# Sheet1.net
KiCad netlist of a schematic drawn in Altium Designer
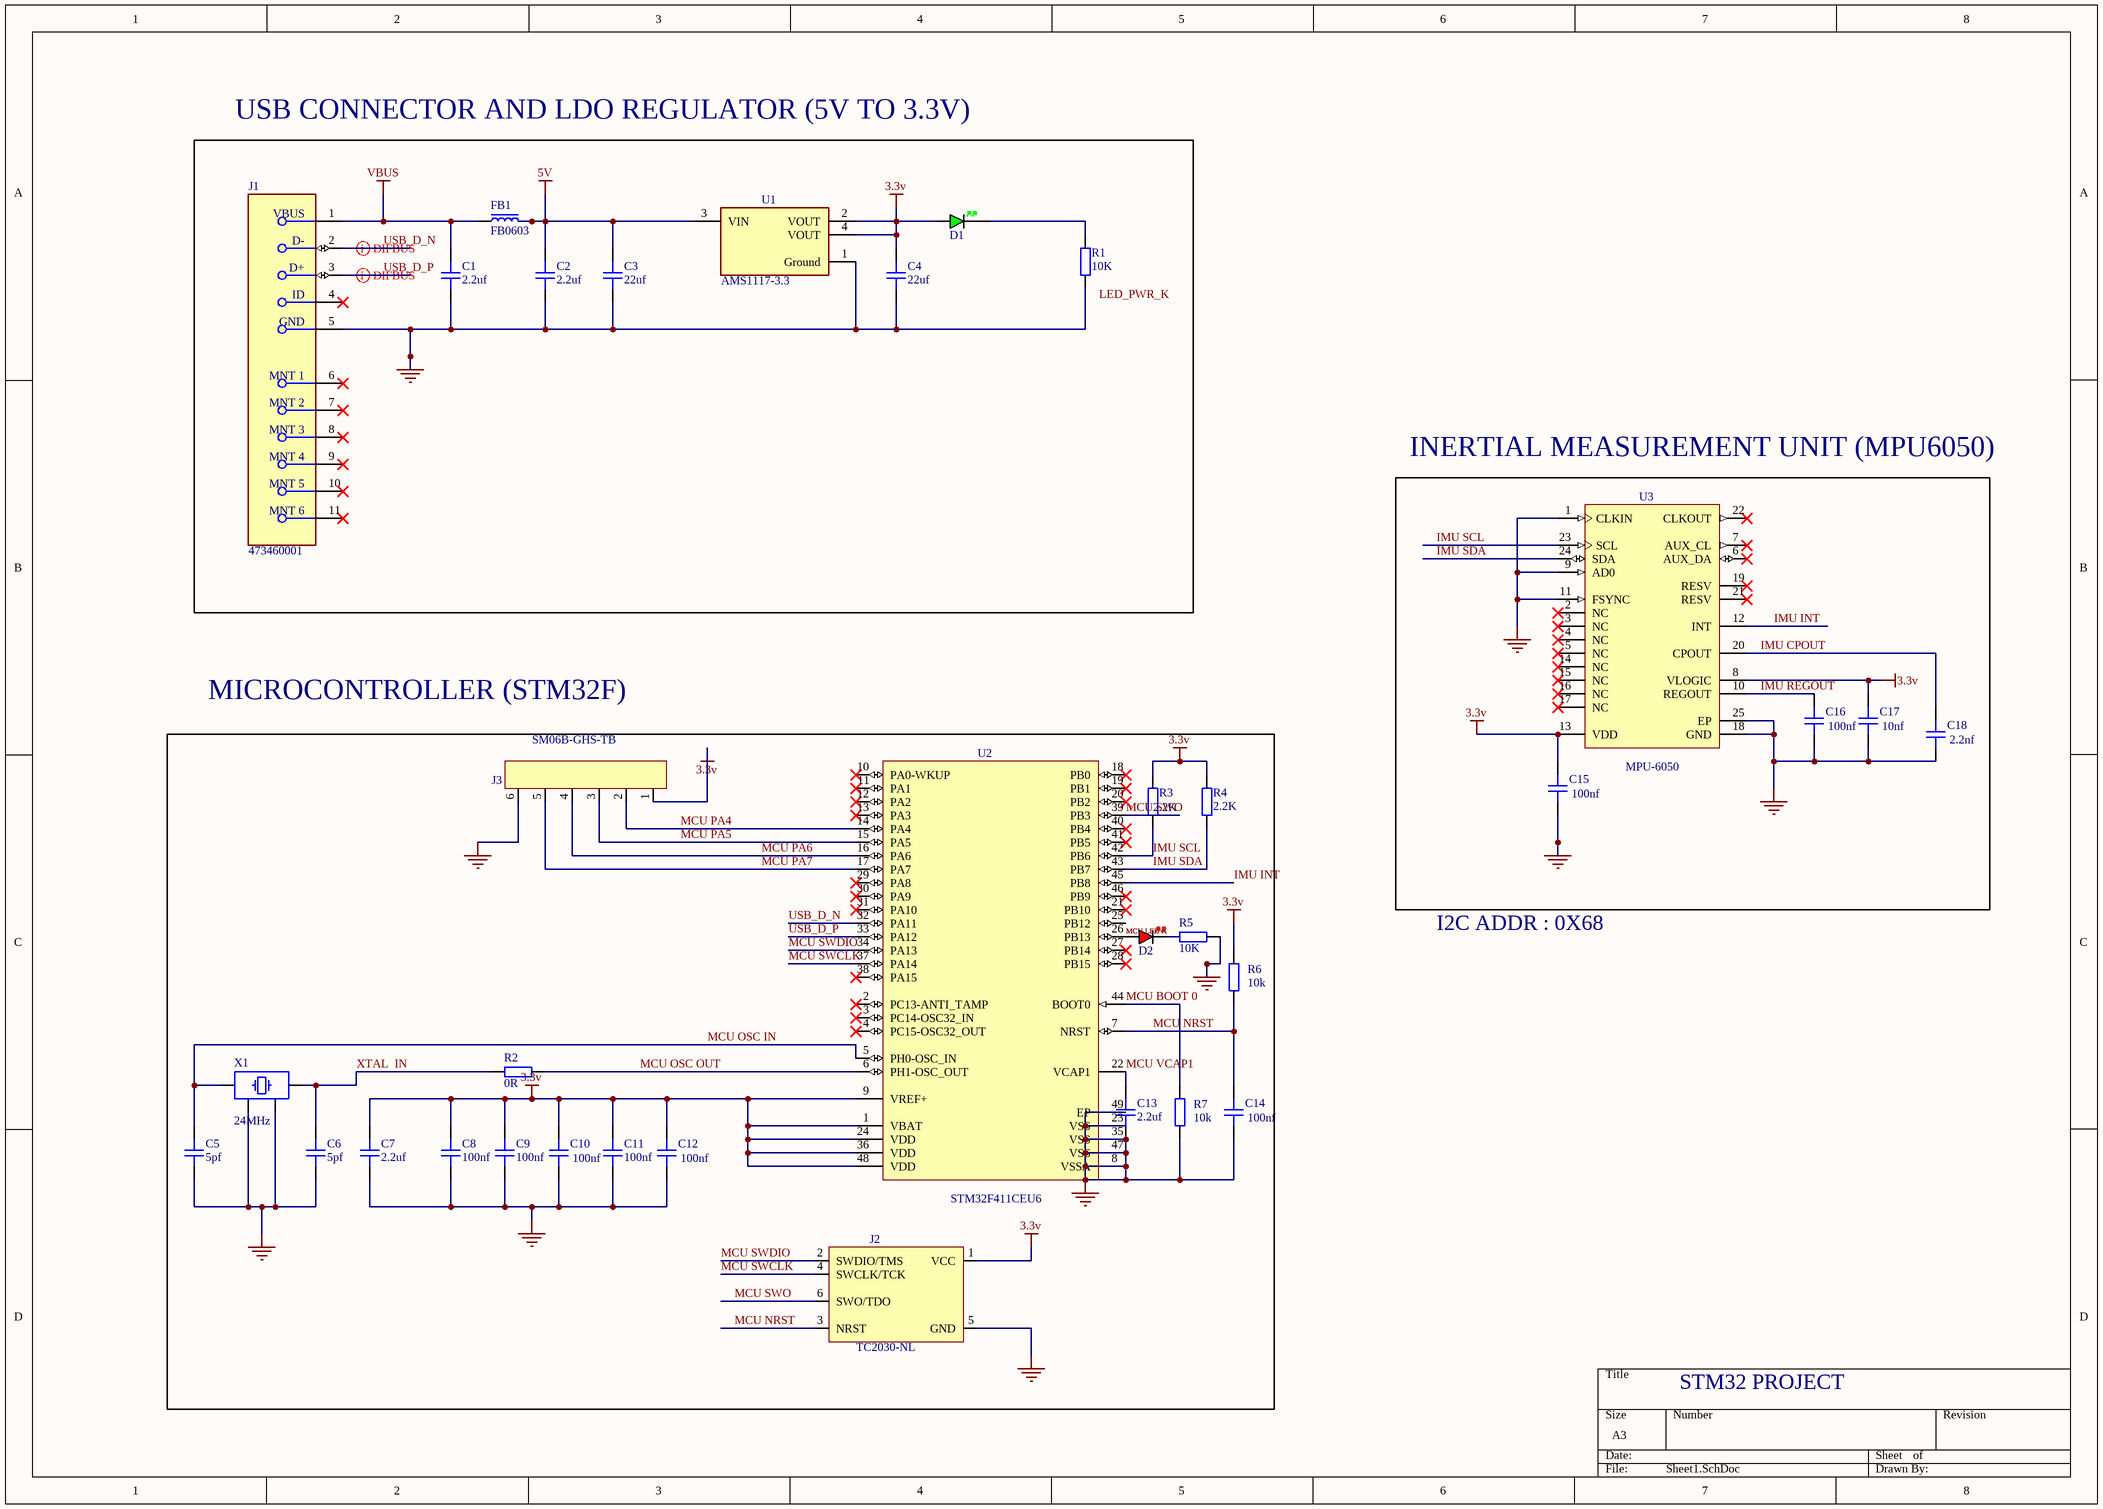
[diagram p0: Sheet1.SchDoc]

(export (version "E")
  (design (tool "Eeschema 10.0.6"))
  (components
    (comp (ref "C1")
      (value "2.2uf")
      (footprint "CAP_0603")
      (description "Capacitor SMD 0603")
      (libsource (lib "Schematic-Lib-PhilsLab") (part "CAP_0603"))
    )
    (comp (ref "C2")
      (value "2.2uf")
      (footprint "CAP_0603")
      (description "Capacitor SMD 0603")
      (libsource (lib "Schematic-Lib-PhilsLab") (part "CAP_0603"))
    )
    (comp (ref "C3")
      (value "22uf")
      (footprint "CAP_0805")
      (description "Capacitor SMD 0805")
      (libsource (lib "Schematic-Lib-PhilsLab") (part "CAP_0805"))
    )
    (comp (ref "C4")
      (value "22uf")
      (footprint "CAP_0805")
      (description "Capacitor SMD 0805")
      (libsource (lib "Schematic-Lib-PhilsLab") (part "CAP_0805"))
    )
    (comp (ref "C5")
      (value "5pf")
      (footprint "CAP_0402")
      (description "Capacitor SMD 0402")
      (libsource (lib "Schematic-Lib-PhilsLab") (part "CAP_0402"))
    )
    (comp (ref "C6")
      (value "5pf")
      (footprint "CAP_0402")
      (description "Capacitor SMD 0402")
      (libsource (lib "Schematic-Lib-PhilsLab") (part "CAP_0402"))
    )
    (comp (ref "C7")
      (value "2.2uf")
      (footprint "CAP_0603")
      (description "Capacitor SMD 0603")
      (libsource (lib "Schematic-Lib-PhilsLab") (part "CAP_0603"))
    )
    (comp (ref "C8")
      (value "100nf")
      (footprint "CAP_0402")
      (description "Capacitor SMD 0402")
      (libsource (lib "Schematic-Lib-PhilsLab") (part "CAP_0402"))
    )
    (comp (ref "C9")
      (value "100nf")
      (footprint "CAP_0402")
      (description "Capacitor SMD 0402")
      (libsource (lib "Schematic-Lib-PhilsLab") (part "CAP_0402"))
    )
    (comp (ref "C10")
      (value "100nf")
      (footprint "CAP_0402")
      (description "Capacitor SMD 0402")
      (libsource (lib "Schematic-Lib-PhilsLab") (part "CAP_0402"))
    )
    (comp (ref "C11")
      (value "100nf")
      (footprint "CAP_0402")
      (description "Capacitor SMD 0402")
      (libsource (lib "Schematic-Lib-PhilsLab") (part "CAP_0402"))
    )
    (comp (ref "C12")
      (value "100nf")
      (footprint "CAP_0402")
      (description "Capacitor SMD 0402")
      (libsource (lib "Schematic-Lib-PhilsLab") (part "CAP_0402"))
    )
    (comp (ref "C13")
      (value "2.2uf")
      (footprint "CAP_0603")
      (description "Capacitor SMD 0603")
      (libsource (lib "Schematic-Lib-PhilsLab") (part "CAP_0603"))
    )
    (comp (ref "C14")
      (value "100nf")
      (footprint "CAP_0402")
      (description "Capacitor SMD 0402")
      (libsource (lib "Schematic-Lib-PhilsLab") (part "CAP_0402"))
    )
    (comp (ref "C15")
      (value "100nf")
      (footprint "CAP_0402")
      (description "Capacitor SMD 0402")
      (libsource (lib "Schematic-Lib-PhilsLab") (part "CAP_0402"))
    )
    (comp (ref "C16")
      (value "100nf")
      (footprint "CAP_0402")
      (description "Capacitor SMD 0402")
      (libsource (lib "Schematic-Lib-PhilsLab") (part "CAP_0402"))
    )
    (comp (ref "C17")
      (value "10nf")
      (footprint "CAP_0402")
      (description "Capacitor SMD 0402")
      (libsource (lib "Schematic-Lib-PhilsLab") (part "CAP_0402"))
    )
    (comp (ref "C18")
      (value "2.2nf")
      (footprint "CAP_0402")
      (description "Capacitor SMD 0402")
      (libsource (lib "Schematic-Lib-PhilsLab") (part "CAP_0402"))
    )
    (comp (ref "D1")
      (value "GREEN")
      (footprint "LED_0402_GREEN")
      (description "LED 0402 GREEN SMD")
      (libsource (lib "Schematic-Lib-PhilsLab") (part "LED_0402_GREEN"))
    )
    (comp (ref "D2")
      (value "RED")
      (footprint "LED_0402_RED")
      (description "LED 0402 RED SMD")
      (libsource (lib "Schematic-Lib-PhilsLab") (part "LED_0402_RED"))
    )
    (comp (ref "FB1")
      (value "FB0603")
      (footprint "FB_0603")
      (description "Ferrite Bead SMD 0603")
      (libsource (lib "Schematic-Lib-PhilsLab") (part "FB_0603"))
    )
    (comp (ref "J1")
      (value "473460001")
      (footprint "FP-473460001-MFG")
      (description "CONN RCPT USB2.0 MICRO B SMD R/A")
      (fields
        (field (name "OCTOPART") "https://octopart.com/47346-0001-molex-7164928")
        (field (name "MANUFACTURER") "Molex")
      )
      (libsource (lib "Altium Content Vault") (part "53ae1f1d9b557310b43ca686e5bb76a"))
    )
    (comp (ref "J2")
      (value "TC2030-NL")
      (footprint "TC2030-NL-FP")
      (description "Tag-Connect No-Solder SWD Debug Connector (No Legs) DO NOT PLACE")
      (fields
        (field (name "MANUFACTURER") "Tag-Connect")
        (field (name "MANUFACTURER PART NUMBER") "TC2030-NL-FP")
      )
      (libsource (lib "Schematic-Lib-PhilsLab") (part "TC2030-NL"))
    )
    (comp (ref "J3")
      (value "SM06B-GHS-TB")
      (footprint "SM06B-GHS-TB")
      (description "Header Connector 6 Position 1.25MM Pitch SMD Horizontal JST GH")
      (fields (field (name "MANUFACTURER") "JST"))
      (libsource (lib "Schematic-Lib-PhilsLab") (part "SM06B-GHS-TB"))
    )
    (comp (ref "R1")
      (value "10K")
      (footprint "RES_0402")
      (description "Resistor SMD 0402")
      (libsource (lib "Schematic-Lib-PhilsLab") (part "RES_0402"))
    )
    (comp (ref "R2")
      (value "0R")
      (footprint "RES_0402")
      (description "Resistor SMD 0402")
      (libsource (lib "Schematic-Lib-PhilsLab") (part "RES_0402"))
    )
    (comp (ref "R3")
      (value "2.2K")
      (footprint "RES_0402")
      (description "Resistor SMD 0402")
      (libsource (lib "Schematic-Lib-PhilsLab") (part "RES_0402"))
    )
    (comp (ref "R4")
      (value "2.2K")
      (footprint "RES_0402")
      (description "Resistor SMD 0402")
      (libsource (lib "Schematic-Lib-PhilsLab") (part "RES_0402"))
    )
    (comp (ref "R5")
      (value "10K")
      (footprint "RES_0402")
      (description "Resistor SMD 0402")
      (libsource (lib "Schematic-Lib-PhilsLab") (part "RES_0402"))
    )
    (comp (ref "R6")
      (value "10k")
      (footprint "RES_0402")
      (description "Resistor SMD 0402")
      (libsource (lib "Schematic-Lib-PhilsLab") (part "RES_0402"))
    )
    (comp (ref "R7")
      (value "10k")
      (footprint "RES_0402")
      (description "Resistor SMD 0402")
      (libsource (lib "Schematic-Lib-PhilsLab") (part "RES_0402"))
    )
    (comp (ref "U1")
      (value "AMS1117-3.3")
      (footprint "FP-AMS1117-IPC_C")
      (description "LDO Voltage Regulators 1A, 3.3V")
      (fields
        (field (name "OCTOPART") "https://octopart.com/ams1117-3.3-advanced+monolithic+systems-25899300")
        (field (name "MANUFACTURER") "Advanced Monolithic Systems")
      )
      (libsource (lib "Altium Content Vault") (part "8bdbb5f8e77002000e30dd2845d0354"))
    )
    (comp (ref "U2")
      (value "STM32F411CEU6")
      (footprint "STM-UFQFPN48_L")
      (libsource (lib "Altium Content Vault") (part "MC-ARM-STM32F411-UFQFPN48"))
    )
    (comp (ref "U3")
      (value "MPU-6050")
      (footprint "IS-QFN-24_V")
      (fields (field (name "MANUFACTURER") "InvenSense"))
      (libsource (lib "Altium Content Vault") (part "IS-MPU-6050-QFN-24"))
    )
    (comp (ref "X1")
      (value "24MHz")
      (footprint "XTAL_3225")
      (description "Crystal SMD 24MHz 10PPM 7pF 3225")
      (fields
        (field (name "MANUFACTURER") "Epson")
        (field (name "MANUFACTURER PART NUMBER") "TSX-3225 24.0000MF15X-AC")
      )
      (libsource (lib "Schematic-Lib-PhilsLab") (part "TSX-3225_24.0000MF15X-AC"))
    )
  )
  (nets
    (net (code "1") (name "/IMU CPOUT") (class "Default")
      (node (ref "C18") (pin "2") (pinfunction "2_2") (pintype "passive"))
      (node (ref "U3") (pin "20") (pinfunction "CPOUT_20") (pintype "passive"))
    )
    (net (code "2") (name "/IMU INT") (class "Default")
      (node (ref "U2") (pin "45") (pinfunction "PB8_45") (pintype "bidirectional"))
      (node (ref "U3") (pin "12") (pinfunction "INT_12") (pintype "open_collector"))
    )
    (net (code "3") (name "/IMU REGOUT") (class "Default")
      (node (ref "C16") (pin "2") (pinfunction "2_2") (pintype "passive"))
      (node (ref "U3") (pin "10") (pinfunction "REGOUT_10") (pintype "passive"))
    )
    (net (code "4") (name "/IMU SCL") (class "Default")
      (node (ref "R3") (pin "1") (pinfunction "1_1") (pintype "passive"))
      (node (ref "U2") (pin "42") (pinfunction "PB6_42") (pintype "bidirectional"))
      (node (ref "U3") (pin "23") (pinfunction "SCL_23") (pintype "input"))
    )
    (net (code "5") (name "/IMU SDA") (class "Default")
      (node (ref "R4") (pin "1") (pinfunction "1_1") (pintype "passive"))
      (node (ref "U2") (pin "43") (pinfunction "PB7_43") (pintype "bidirectional"))
      (node (ref "U3") (pin "24") (pinfunction "SDA_24") (pintype "bidirectional"))
    )
    (net (code "7") (name "/MCU BOOT 0") (class "Default")
      (node (ref "R7") (pin "1") (pinfunction "1_1") (pintype "passive"))
      (node (ref "U2") (pin "44") (pinfunction "BOOT0_44") (pintype "input"))
    )
    (net (code "8") (name "/MCU LED A") (class "Default")
      (node (ref "D2") (pin "A") (pinfunction "A_A") (pintype "passive"))
      (node (ref "U2") (pin "26") (pinfunction "PB13_26") (pintype "bidirectional"))
    )
    (net (code "9") (name "/MCU NRST") (class "Default")
      (node (ref "C14") (pin "2") (pinfunction "2_2") (pintype "passive"))
      (node (ref "J2") (pin "3") (pinfunction "NRST_3") (pintype "passive"))
      (node (ref "R6") (pin "2") (pinfunction "2_2") (pintype "passive"))
      (node (ref "U2") (pin "7") (pinfunction "NRST_7") (pintype "bidirectional"))
    )
    (net (code "10") (name "/MCU OSC IN") (class "Default")
      (node (ref "C5") (pin "2") (pinfunction "2_2") (pintype "passive"))
      (node (ref "U2") (pin "5") (pinfunction "PH0-OSC_IN_5") (pintype "bidirectional"))
      (node (ref "X1") (pin "1") (pinfunction "1_1") (pintype "passive"))
    )
    (net (code "11") (name "/MCU OSC OUT") (class "Default")
      (node (ref "R2") (pin "2") (pinfunction "2_2") (pintype "passive"))
      (node (ref "U2") (pin "6") (pinfunction "PH1-OSC_OUT_6") (pintype "bidirectional"))
    )
    (net (code "12") (name "/MCU PA4") (class "Default")
      (node (ref "J3") (pin "2") (pinfunction "2_2") (pintype "passive"))
      (node (ref "U2") (pin "14") (pinfunction "PA4_14") (pintype "bidirectional"))
    )
    (net (code "13") (name "/MCU PA5") (class "Default")
      (node (ref "J3") (pin "3") (pinfunction "3_3") (pintype "passive"))
      (node (ref "U2") (pin "15") (pinfunction "PA5_15") (pintype "bidirectional"))
    )
    (net (code "14") (name "/MCU PA6") (class "Default")
      (node (ref "J3") (pin "4") (pinfunction "4_4") (pintype "passive"))
      (node (ref "U2") (pin "16") (pinfunction "PA6_16") (pintype "bidirectional"))
    )
    (net (code "15") (name "/MCU PA7") (class "Default")
      (node (ref "J3") (pin "5") (pinfunction "5_5") (pintype "passive"))
      (node (ref "U2") (pin "17") (pinfunction "PA7_17") (pintype "bidirectional"))
    )
    (net (code "16") (name "/MCU SWCLK") (class "Default")
      (node (ref "J2") (pin "4") (pinfunction "SWCLK/TCK_4") (pintype "passive"))
      (node (ref "U2") (pin "37") (pinfunction "PA14_37") (pintype "bidirectional"))
    )
    (net (code "17") (name "/MCU SWDIO") (class "Default")
      (node (ref "J2") (pin "2") (pinfunction "SWDIO/TMS_2") (pintype "passive"))
      (node (ref "U2") (pin "34") (pinfunction "PA13_34") (pintype "bidirectional"))
    )
    (net (code "18") (name "/MCU SWO") (class "Default")
      (node (ref "J2") (pin "6") (pinfunction "SWO/TDO_6") (pintype "passive"))
      (node (ref "U2") (pin "39") (pinfunction "PB3_39") (pintype "bidirectional"))
    )
    (net (code "19") (name "/MCU VCAP1") (class "Default")
      (node (ref "C13") (pin "2") (pinfunction "2_2") (pintype "passive"))
      (node (ref "U2") (pin "22") (pinfunction "VCAP1_22") (pintype "passive"))
    )
    (net (code "20") (name "/USB_D_N") (class "Default")
      (node (ref "J1") (pin "2") (pinfunction "D-_2") (pintype "bidirectional"))
      (node (ref "U2") (pin "32") (pinfunction "PA11_32") (pintype "bidirectional"))
    )
    (net (code "21") (name "/USB_D_P") (class "Default")
      (node (ref "J1") (pin "3") (pinfunction "D+_3") (pintype "bidirectional"))
      (node (ref "U2") (pin "33") (pinfunction "PA12_33") (pintype "bidirectional"))
    )
    (net (code "22") (name "/XTAL  IN") (class "Default")
      (node (ref "C6") (pin "2") (pinfunction "2_2") (pintype "passive"))
      (node (ref "R2") (pin "1") (pinfunction "1_1") (pintype "passive"))
      (node (ref "X1") (pin "3") (pinfunction "3_3") (pintype "passive"))
    )
    (net (code "23") (name "3.3v") (class "Default")
      (node (ref "C10") (pin "2") (pinfunction "2_2") (pintype "passive"))
      (node (ref "C11") (pin "2") (pinfunction "2_2") (pintype "passive"))
      (node (ref "C12") (pin "2") (pinfunction "2_2") (pintype "passive"))
      (node (ref "C15") (pin "2") (pinfunction "2_2") (pintype "passive"))
      (node (ref "C17") (pin "2") (pinfunction "2_2") (pintype "passive"))
      (node (ref "C4") (pin "2") (pinfunction "2_2") (pintype "passive"))
      (node (ref "C7") (pin "2") (pinfunction "2_2") (pintype "passive"))
      (node (ref "C8") (pin "2") (pinfunction "2_2") (pintype "passive"))
      (node (ref "C9") (pin "2") (pinfunction "2_2") (pintype "passive"))
      (node (ref "D1") (pin "A") (pinfunction "A_A") (pintype "passive"))
      (node (ref "J2") (pin "1") (pinfunction "VCC_1") (pintype "passive"))
      (node (ref "J3") (pin "1") (pinfunction "1_1") (pintype "passive"))
      (node (ref "R3") (pin "2") (pinfunction "2_2") (pintype "passive"))
      (node (ref "R4") (pin "2") (pinfunction "2_2") (pintype "passive"))
      (node (ref "R6") (pin "1") (pinfunction "1_1") (pintype "passive"))
      (node (ref "U1") (pin "2") (pinfunction "VOUT_2") (pintype "passive"))
      (node (ref "U1") (pin "4") (pinfunction "VOUT_4") (pintype "passive"))
      (node (ref "U2") (pin "1") (pinfunction "VBAT_1") (pintype "power_in"))
      (node (ref "U2") (pin "24") (pinfunction "VDD_24") (pintype "power_in"))
      (node (ref "U2") (pin "36") (pinfunction "VDD_36") (pintype "power_in"))
      (node (ref "U2") (pin "48") (pinfunction "VDD_48") (pintype "power_in"))
      (node (ref "U2") (pin "9") (pinfunction "VREF+_9") (pintype "power_in"))
      (node (ref "U3") (pin "13") (pinfunction "VDD_13") (pintype "power_in"))
      (node (ref "U3") (pin "8") (pinfunction "VLOGIC_8") (pintype "power_in"))
    )
    (net (code "24") (name "5V") (class "Default")
      (node (ref "C2") (pin "2") (pinfunction "2_2") (pintype "passive"))
      (node (ref "C3") (pin "2") (pinfunction "2_2") (pintype "passive"))
      (node (ref "FB1") (pin "2") (pinfunction "2_2") (pintype "passive"))
      (node (ref "U1") (pin "3") (pinfunction "VIN_3") (pintype "power_in"))
    )
    (net (code "25") (name "GND") (class "Default")
      (node (ref "C1") (pin "1") (pinfunction "1_1") (pintype "passive"))
      (node (ref "C10") (pin "1") (pinfunction "1_1") (pintype "passive"))
      (node (ref "C11") (pin "1") (pinfunction "1_1") (pintype "passive"))
      (node (ref "C12") (pin "1") (pinfunction "1_1") (pintype "passive"))
      (node (ref "C13") (pin "1") (pinfunction "1_1") (pintype "passive"))
      (node (ref "C14") (pin "1") (pinfunction "1_1") (pintype "passive"))
      (node (ref "C15") (pin "1") (pinfunction "1_1") (pintype "passive"))
      (node (ref "C16") (pin "1") (pinfunction "1_1") (pintype "passive"))
      (node (ref "C17") (pin "1") (pinfunction "1_1") (pintype "passive"))
      (node (ref "C18") (pin "1") (pinfunction "1_1") (pintype "passive"))
      (node (ref "C2") (pin "1") (pinfunction "1_1") (pintype "passive"))
      (node (ref "C3") (pin "1") (pinfunction "1_1") (pintype "passive"))
      (node (ref "C4") (pin "1") (pinfunction "1_1") (pintype "passive"))
      (node (ref "C5") (pin "1") (pinfunction "1_1") (pintype "passive"))
      (node (ref "C6") (pin "1") (pinfunction "1_1") (pintype "passive"))
      (node (ref "C7") (pin "1") (pinfunction "1_1") (pintype "passive"))
      (node (ref "C8") (pin "1") (pinfunction "1_1") (pintype "passive"))
      (node (ref "C9") (pin "1") (pinfunction "1_1") (pintype "passive"))
      (node (ref "J1") (pin "5") (pinfunction "GND_5") (pintype "power_in"))
      (node (ref "J2") (pin "5") (pinfunction "GND_5") (pintype "passive"))
      (node (ref "J3") (pin "6") (pinfunction "6_6") (pintype "passive"))
      (node (ref "R1") (pin "1") (pinfunction "1_1") (pintype "passive"))
      (node (ref "R5") (pin "1") (pinfunction "1_1") (pintype "passive"))
      (node (ref "R7") (pin "2") (pinfunction "2_2") (pintype "passive"))
      (node (ref "U1") (pin "1") (pinfunction "Ground_1") (pintype "power_in"))
      (node (ref "U2") (pin "23") (pinfunction "VSS_23") (pintype "power_in"))
      (node (ref "U2") (pin "35") (pinfunction "VSS_35") (pintype "power_in"))
      (node (ref "U2") (pin "47") (pinfunction "VSS_47") (pintype "power_in"))
      (node (ref "U2") (pin "49") (pinfunction "EP_49") (pintype "power_in"))
      (node (ref "U2") (pin "8") (pinfunction "VSSA_8") (pintype "power_in"))
      (node (ref "U3") (pin "1") (pinfunction "CLKIN_1") (pintype "input"))
      (node (ref "U3") (pin "11") (pinfunction "FSYNC_11") (pintype "input"))
      (node (ref "U3") (pin "18") (pinfunction "GND_18") (pintype "power_in"))
      (node (ref "U3") (pin "25") (pinfunction "EP_25") (pintype "power_in"))
      (node (ref "U3") (pin "9") (pinfunction "AD0_9") (pintype "input"))
      (node (ref "X1") (pin "2") (pinfunction "2_2") (pintype "passive"))
      (node (ref "X1") (pin "4") (pinfunction "4_4") (pintype "passive"))
    )
    (net (code "26") (name "Net-(D1-PadK)") (class "Default")
      (node (ref "D1") (pin "K") (pinfunction "K_K") (pintype "passive"))
      (node (ref "R1") (pin "2") (pinfunction "2_2") (pintype "passive"))
    )
    (net (code "27") (name "Net-(D2-PadK)") (class "Default")
      (node (ref "D2") (pin "K") (pinfunction "K_K") (pintype "passive"))
      (node (ref "R5") (pin "2") (pinfunction "2_2") (pintype "passive"))
    )
    (net (code "28") (name "VBUS") (class "Default")
      (node (ref "C1") (pin "2") (pinfunction "2_2") (pintype "passive"))
      (node (ref "FB1") (pin "1") (pinfunction "1_1") (pintype "passive"))
      (node (ref "J1") (pin "1") (pinfunction "VBUS_1") (pintype "power_in"))
    )
    (net (code "29") (name "unconnected-(J1-ID-Pad4)") (class "Default")
      (node (ref "J1") (pin "4") (pinfunction "ID_4") (pintype "passive+no_connect"))
    )
    (net (code "30") (name "unconnected-(J1-MNT_1-Pad6)") (class "Default")
      (node (ref "J1") (pin "6") (pinfunction "MNT_1_6") (pintype "passive+no_connect"))
    )
    (net (code "31") (name "unconnected-(J1-MNT_2-Pad7)") (class "Default")
      (node (ref "J1") (pin "7") (pinfunction "MNT_2_7") (pintype "passive+no_connect"))
    )
    (net (code "32") (name "unconnected-(J1-MNT_3-Pad8)") (class "Default")
      (node (ref "J1") (pin "8") (pinfunction "MNT_3_8") (pintype "passive+no_connect"))
    )
    (net (code "33") (name "unconnected-(J1-MNT_4-Pad9)") (class "Default")
      (node (ref "J1") (pin "9") (pinfunction "MNT_4_9") (pintype "passive+no_connect"))
    )
    (net (code "34") (name "unconnected-(J1-MNT_5-Pad10)") (class "Default")
      (node (ref "J1") (pin "10") (pinfunction "MNT_5_10") (pintype "passive+no_connect"))
    )
    (net (code "35") (name "unconnected-(J1-MNT_6-Pad11)") (class "Default")
      (node (ref "J1") (pin "11") (pinfunction "MNT_6_11") (pintype "passive+no_connect"))
    )
    (net (code "36") (name "unconnected-(U2-PA0-WKUP-Pad10)") (class "Default")
      (node (ref "U2") (pin "10") (pinfunction "PA0-WKUP_10") (pintype "bidirectional+no_connect"))
    )
    (net (code "37") (name "unconnected-(U2-PA1-Pad11)") (class "Default")
      (node (ref "U2") (pin "11") (pinfunction "PA1_11") (pintype "bidirectional+no_connect"))
    )
    (net (code "38") (name "unconnected-(U2-PA2-Pad12)") (class "Default")
      (node (ref "U2") (pin "12") (pinfunction "PA2_12") (pintype "bidirectional+no_connect"))
    )
    (net (code "39") (name "unconnected-(U2-PA3-Pad13)") (class "Default")
      (node (ref "U2") (pin "13") (pinfunction "PA3_13") (pintype "bidirectional+no_connect"))
    )
    (net (code "40") (name "unconnected-(U2-PA8-Pad29)") (class "Default")
      (node (ref "U2") (pin "29") (pinfunction "PA8_29") (pintype "bidirectional+no_connect"))
    )
    (net (code "41") (name "unconnected-(U2-PA9-Pad30)") (class "Default")
      (node (ref "U2") (pin "30") (pinfunction "PA9_30") (pintype "bidirectional+no_connect"))
    )
    (net (code "42") (name "unconnected-(U2-PA10-Pad31)") (class "Default")
      (node (ref "U2") (pin "31") (pinfunction "PA10_31") (pintype "bidirectional+no_connect"))
    )
    (net (code "43") (name "unconnected-(U2-PA15-Pad38)") (class "Default")
      (node (ref "U2") (pin "38") (pinfunction "PA15_38") (pintype "bidirectional+no_connect"))
    )
    (net (code "44") (name "unconnected-(U2-PB0-Pad18)") (class "Default")
      (node (ref "U2") (pin "18") (pinfunction "PB0_18") (pintype "bidirectional+no_connect"))
    )
    (net (code "45") (name "unconnected-(U2-PB1-Pad19)") (class "Default")
      (node (ref "U2") (pin "19") (pinfunction "PB1_19") (pintype "bidirectional+no_connect"))
    )
    (net (code "46") (name "unconnected-(U2-PB2-Pad20)") (class "Default")
      (node (ref "U2") (pin "20") (pinfunction "PB2_20") (pintype "bidirectional+no_connect"))
    )
    (net (code "47") (name "unconnected-(U2-PB4-Pad40)") (class "Default")
      (node (ref "U2") (pin "40") (pinfunction "PB4_40") (pintype "bidirectional+no_connect"))
    )
    (net (code "48") (name "unconnected-(U2-PB5-Pad41)") (class "Default")
      (node (ref "U2") (pin "41") (pinfunction "PB5_41") (pintype "bidirectional+no_connect"))
    )
    (net (code "49") (name "unconnected-(U2-PB9-Pad46)") (class "Default")
      (node (ref "U2") (pin "46") (pinfunction "PB9_46") (pintype "bidirectional+no_connect"))
    )
    (net (code "50") (name "unconnected-(U2-PB10-Pad21)") (class "Default")
      (node (ref "U2") (pin "21") (pinfunction "PB10_21") (pintype "bidirectional+no_connect"))
    )
    (net (code "51") (name "unconnected-(U2-PB12-Pad25)") (class "Default")
      (node (ref "U2") (pin "25") (pinfunction "PB12_25") (pintype "bidirectional"))
    )
    (net (code "52") (name "unconnected-(U2-PB14-Pad27)") (class "Default")
      (node (ref "U2") (pin "27") (pinfunction "PB14_27") (pintype "bidirectional+no_connect"))
    )
    (net (code "53") (name "unconnected-(U2-PB15-Pad28)") (class "Default")
      (node (ref "U2") (pin "28") (pinfunction "PB15_28") (pintype "bidirectional+no_connect"))
    )
    (net (code "54") (name "unconnected-(U2-PC13-ANTI_TAMP-Pad2)") (class "Default")
      (node (ref "U2") (pin "2") (pinfunction "PC13-ANTI_TAMP_2") (pintype "bidirectional+no_connect"))
    )
    (net (code "55") (name "unconnected-(U2-PC14-OSC32_IN-Pad3)") (class "Default")
      (node (ref "U2") (pin "3") (pinfunction "PC14-OSC32_IN_3") (pintype "bidirectional+no_connect"))
    )
    (net (code "56") (name "unconnected-(U2-PC15-OSC32_OUT-Pad4)") (class "Default")
      (node (ref "U2") (pin "4") (pinfunction "PC15-OSC32_OUT_4") (pintype "bidirectional+no_connect"))
    )
    (net (code "57") (name "unconnected-(U3-AUX_CL-Pad7)") (class "Default")
      (node (ref "U3") (pin "7") (pinfunction "AUX_CL_7") (pintype "output+no_connect"))
    )
    (net (code "58") (name "unconnected-(U3-AUX_DA-Pad6)") (class "Default")
      (node (ref "U3") (pin "6") (pinfunction "AUX_DA_6") (pintype "bidirectional+no_connect"))
    )
    (net (code "59") (name "unconnected-(U3-CLKOUT-Pad22)") (class "Default")
      (node (ref "U3") (pin "22") (pinfunction "CLKOUT_22") (pintype "output+no_connect"))
    )
    (net (code "60") (name "unconnected-(U3-NC-Pad2)") (class "Default")
      (node (ref "U3") (pin "2") (pinfunction "NC_2") (pintype "passive+no_connect"))
    )
    (net (code "61") (name "unconnected-(U3-NC-Pad3)") (class "Default")
      (node (ref "U3") (pin "3") (pinfunction "NC_3") (pintype "passive+no_connect"))
    )
    (net (code "62") (name "unconnected-(U3-NC-Pad4)") (class "Default")
      (node (ref "U3") (pin "4") (pinfunction "NC_4") (pintype "passive+no_connect"))
    )
    (net (code "63") (name "unconnected-(U3-NC-Pad5)") (class "Default")
      (node (ref "U3") (pin "5") (pinfunction "NC_5") (pintype "passive+no_connect"))
    )
    (net (code "64") (name "unconnected-(U3-NC-Pad14)") (class "Default")
      (node (ref "U3") (pin "14") (pinfunction "NC_14") (pintype "passive+no_connect"))
    )
    (net (code "65") (name "unconnected-(U3-NC-Pad15)") (class "Default")
      (node (ref "U3") (pin "15") (pinfunction "NC_15") (pintype "passive+no_connect"))
    )
    (net (code "66") (name "unconnected-(U3-NC-Pad16)") (class "Default")
      (node (ref "U3") (pin "16") (pinfunction "NC_16") (pintype "passive+no_connect"))
    )
    (net (code "67") (name "unconnected-(U3-NC-Pad17)") (class "Default")
      (node (ref "U3") (pin "17") (pinfunction "NC_17") (pintype "passive+no_connect"))
    )
    (net (code "68") (name "unconnected-(U3-RESV-Pad19)") (class "Default")
      (node (ref "U3") (pin "19") (pinfunction "RESV_19") (pintype "passive+no_connect"))
    )
    (net (code "69") (name "unconnected-(U3-RESV-Pad21)") (class "Default")
      (node (ref "U3") (pin "21") (pinfunction "RESV_21") (pintype "passive+no_connect"))
    )
  )
)
